# WWOL_phy.net
KiCad netlist of a schematic drawn in Altium Designer
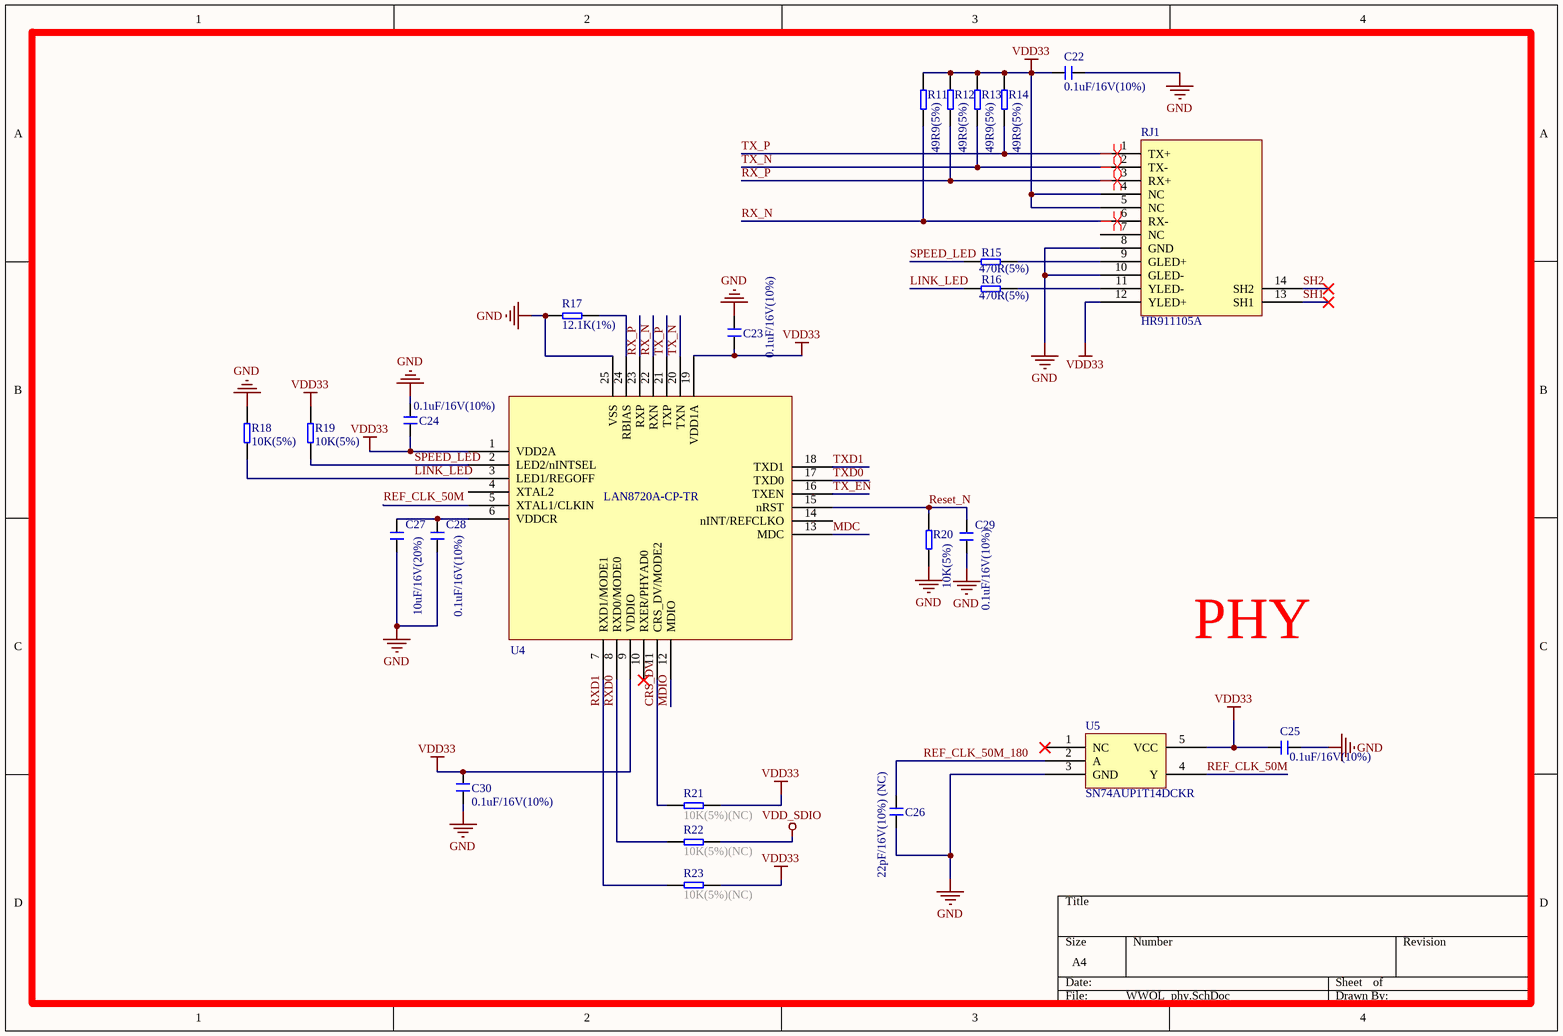
[diagram p0: WWOL_phy.SchDoc]

(export (version "E")
  (design (tool "Eeschema 10.0.6"))
  (components
    (comp (ref "C22")
      (value "0.1uF/16V(10%)")
      (footprint "C0402")
      (description "无极性贴片电容")
      (fields (field (name "版权归属") "源创客"))
      (libsource (lib "WWOL") (part "C"))
    )
    (comp (ref "C23")
      (value "0.1uF/16V(10%)")
      (footprint "C0402")
      (description "无极性贴片电容")
      (fields (field (name "版权归属") "源创客"))
      (libsource (lib "WWOL") (part "C"))
    )
    (comp (ref "C24")
      (value "0.1uF/16V(10%)")
      (footprint "C0402")
      (description "无极性贴片电容")
      (fields (field (name "版权归属") "源创客"))
      (libsource (lib "WWOL") (part "C"))
    )
    (comp (ref "C25")
      (value "0.1uF/16V(10%)")
      (footprint "C0402")
      (description "无极性贴片电容")
      (fields (field (name "版权归属") "源创客"))
      (libsource (lib "WWOL") (part "C"))
    )
    (comp (ref "C26")
      (value "22pF/16V(10%) (NC)")
      (footprint "C0402")
      (description "无极性贴片电容")
      (fields (field (name "版权归属") "源创客"))
      (libsource (lib "WWOL") (part "C"))
    )
    (comp (ref "C27")
      (value "10uF/16V(20%)")
      (footprint "C0402")
      (description "无极性贴片电容")
      (fields (field (name "版权归属") "源创客"))
      (libsource (lib "WWOL") (part "C"))
    )
    (comp (ref "C28")
      (value "0.1uF/16V(10%)")
      (footprint "C0402")
      (description "无极性贴片电容")
      (fields (field (name "版权归属") "源创客"))
      (libsource (lib "WWOL") (part "C"))
    )
    (comp (ref "C29")
      (value "0.1uF/16V(10%)")
      (footprint "C0402")
      (description "无极性贴片电容")
      (fields (field (name "版权归属") "源创客"))
      (libsource (lib "WWOL") (part "C"))
    )
    (comp (ref "C30")
      (value "0.1uF/16V(10%)")
      (footprint "C0402")
      (description "无极性贴片电容")
      (fields (field (name "版权归属") "源创客"))
      (libsource (lib "WWOL") (part "C"))
    )
    (comp (ref "R11")
      (value "49R9(5%)")
      (footprint "R0402")
      (description "贴片电阻")
      (libsource (lib "WWOL") (part "R"))
    )
    (comp (ref "R12")
      (value "49R9(5%)")
      (footprint "R0402")
      (description "贴片电阻")
      (libsource (lib "WWOL") (part "R"))
    )
    (comp (ref "R13")
      (value "49R9(5%)")
      (footprint "R0402")
      (description "贴片电阻")
      (libsource (lib "WWOL") (part "R"))
    )
    (comp (ref "R14")
      (value "49R9(5%)")
      (footprint "R0402")
      (description "贴片电阻")
      (libsource (lib "WWOL") (part "R"))
    )
    (comp (ref "R15")
      (value "470R(5%)")
      (footprint "R0402")
      (description "贴片电阻")
      (libsource (lib "WWOL") (part "R"))
    )
    (comp (ref "R16")
      (value "470R(5%)")
      (footprint "R0402")
      (description "贴片电阻")
      (libsource (lib "WWOL") (part "R"))
    )
    (comp (ref "R17")
      (value "12.1K(1%)")
      (footprint "R0402")
      (description "贴片电阻")
      (libsource (lib "WWOL") (part "R"))
    )
    (comp (ref "R18")
      (value "10K(5%)")
      (footprint "R0402")
      (description "贴片电阻")
      (libsource (lib "WWOL") (part "R"))
    )
    (comp (ref "R19")
      (value "10K(5%)")
      (footprint "R0402")
      (description "贴片电阻")
      (libsource (lib "WWOL") (part "R"))
    )
    (comp (ref "R20")
      (value "10K(5%)")
      (footprint "R0402")
      (description "贴片电阻")
      (libsource (lib "WWOL") (part "R"))
    )
    (comp (ref "R21")
      (value "10K(5%)(NC)")
      (footprint "R0402")
      (description "贴片电阻")
      (libsource (lib "WWOL") (part "R"))
    )
    (comp (ref "R22")
      (value "10K(5%)(NC)")
      (footprint "R0402")
      (description "贴片电阻")
      (libsource (lib "WWOL") (part "R"))
    )
    (comp (ref "R23")
      (value "10K(5%)(NC)")
      (footprint "R0402")
      (description "贴片电阻")
      (libsource (lib "WWOL") (part "R"))
    )
    (comp (ref "RJ1")
      (value "HR911105A")
      (footprint "RJ-45A12")
      (description "带灯以太网接口")
      (libsource (lib "WWOL") (part "HR911105A"))
    )
    (comp (ref "U4")
      (value "LAN8720A-CP-TR")
      (footprint "QFN50P400X400X100_HS-25N")
      (description "以太网phy")
      (libsource (lib "WWOL") (part "LAN8720A-CP-TR"))
    )
    (comp (ref "U5")
      (value "SN74AUP1T14DCKR")
      (footprint "SC-70-5_L2.1-W1.3-P0.65-LS2.1-BR")
      (description "反相器")
      (libsource (lib "WWOL") (part "SN74AUP1T14DCKR"))
    )
  )
  (nets
    (net (code "1") (name "/CRS_DV") (class "Default")
      (node (ref "R21") (pin "1") (pinfunction "1_1") (pintype "passive"))
      (node (ref "U4") (pin "11") (pinfunction "CRS_DV/MODE2_11") (pintype "passive"))
    )
    (net (code "2") (name "/LINK_LED") (class "Default")
      (node (ref "R16") (pin "2") (pinfunction "2_2") (pintype "passive"))
      (node (ref "R18") (pin "2") (pinfunction "2_2") (pintype "passive"))
      (node (ref "U4") (pin "3") (pinfunction "LED1/REGOFF_3") (pintype "passive"))
    )
    (net (code "3") (name "/MDC") (class "Default")
      (node (ref "U4") (pin "13") (pinfunction "MDC_13") (pintype "passive"))
    )
    (net (code "4") (name "/MDIO") (class "Default")
      (node (ref "U4") (pin "12") (pinfunction "MDIO_12") (pintype "passive"))
    )
    (net (code "5") (name "/REF_CLK_50M") (class "Default")
      (node (ref "U4") (pin "5") (pinfunction "XTAL1/CLKIN_5") (pintype "passive"))
      (node (ref "U5") (pin "4") (pinfunction "Y_4") (pintype "passive"))
    )
    (net (code "6") (name "/REF_CLK_50M_180") (class "Default")
      (node (ref "C26") (pin "1") (pinfunction "1_1") (pintype "passive"))
      (node (ref "U5") (pin "2") (pinfunction "A_2") (pintype "passive"))
    )
    (net (code "7") (name "/RXD0") (class "Default")
      (node (ref "R22") (pin "1") (pinfunction "1_1") (pintype "passive"))
      (node (ref "U4") (pin "8") (pinfunction "RXD0/MODE0_8") (pintype "passive"))
    )
    (net (code "8") (name "/RXD1") (class "Default")
      (node (ref "R23") (pin "1") (pinfunction "1_1") (pintype "passive"))
      (node (ref "U4") (pin "7") (pinfunction "RXD1/MODE1_7") (pintype "passive"))
    )
    (net (code "9") (name "/RX_N") (class "Default")
      (node (ref "R11") (pin "2") (pinfunction "2_2") (pintype "passive"))
      (node (ref "RJ1") (pin "6") (pinfunction "RX-_6") (pintype "passive"))
      (node (ref "U4") (pin "22") (pinfunction "RXN_22") (pintype "passive"))
    )
    (net (code "10") (name "/RX_P") (class "Default")
      (node (ref "R12") (pin "2") (pinfunction "2_2") (pintype "passive"))
      (node (ref "RJ1") (pin "3") (pinfunction "RX+_3") (pintype "passive"))
      (node (ref "U4") (pin "23") (pinfunction "RXP_23") (pintype "passive"))
    )
    (net (code "11") (name "/Reset_N") (class "Default")
      (node (ref "C29") (pin "2") (pinfunction "2_2") (pintype "passive"))
      (node (ref "R20") (pin "2") (pinfunction "2_2") (pintype "passive"))
      (node (ref "U4") (pin "15") (pinfunction "nRST_15") (pintype "passive"))
    )
    (net (code "12") (name "/SH1") (class "Default")
      (node (ref "RJ1") (pin "13") (pinfunction "SH1_13") (pintype "passive+no_connect"))
    )
    (net (code "13") (name "/SH2") (class "Default")
      (node (ref "RJ1") (pin "14") (pinfunction "SH2_14") (pintype "passive+no_connect"))
    )
    (net (code "14") (name "/SPEED_LED") (class "Default")
      (node (ref "R15") (pin "2") (pinfunction "2_2") (pintype "passive"))
      (node (ref "R19") (pin "2") (pinfunction "2_2") (pintype "passive"))
      (node (ref "U4") (pin "2") (pinfunction "LED2/nINTSEL_2") (pintype "passive"))
    )
    (net (code "15") (name "/TXD0") (class "Default")
      (node (ref "U4") (pin "17") (pinfunction "TXD0_17") (pintype "passive"))
    )
    (net (code "16") (name "/TXD1") (class "Default")
      (node (ref "U4") (pin "18") (pinfunction "TXD1_18") (pintype "passive"))
    )
    (net (code "17") (name "/TX_EN") (class "Default")
      (node (ref "U4") (pin "16") (pinfunction "TXEN_16") (pintype "passive"))
    )
    (net (code "18") (name "/TX_N") (class "Default")
      (node (ref "R13") (pin "2") (pinfunction "2_2") (pintype "passive"))
      (node (ref "RJ1") (pin "2") (pinfunction "TX-_2") (pintype "passive"))
      (node (ref "U4") (pin "20") (pinfunction "TXN_20") (pintype "passive"))
    )
    (net (code "19") (name "/TX_P") (class "Default")
      (node (ref "R14") (pin "2") (pinfunction "2_2") (pintype "passive"))
      (node (ref "RJ1") (pin "1") (pinfunction "TX+_1") (pintype "passive"))
      (node (ref "U4") (pin "21") (pinfunction "TXP_21") (pintype "passive"))
    )
    (net (code "20") (name "GND") (class "Default")
      (node (ref "C22") (pin "2") (pinfunction "2_2") (pintype "passive"))
      (node (ref "C23") (pin "2") (pinfunction "2_2") (pintype "passive"))
      (node (ref "C24") (pin "1") (pinfunction "1_1") (pintype "passive"))
      (node (ref "C25") (pin "1") (pinfunction "1_1") (pintype "passive"))
      (node (ref "C26") (pin "2") (pinfunction "2_2") (pintype "passive"))
      (node (ref "C27") (pin "1") (pinfunction "1_1") (pintype "passive"))
      (node (ref "C28") (pin "1") (pinfunction "1_1") (pintype "passive"))
      (node (ref "C29") (pin "1") (pinfunction "1_1") (pintype "passive"))
      (node (ref "C30") (pin "1") (pinfunction "1_1") (pintype "passive"))
      (node (ref "R17") (pin "2") (pinfunction "2_2") (pintype "passive"))
      (node (ref "R18") (pin "1") (pinfunction "1_1") (pintype "passive"))
      (node (ref "R20") (pin "1") (pinfunction "1_1") (pintype "passive"))
      (node (ref "RJ1") (pin "10") (pinfunction "GLED-_10") (pintype "passive"))
      (node (ref "RJ1") (pin "8") (pinfunction "GND_8") (pintype "passive"))
      (node (ref "U4") (pin "25") (pinfunction "VSS_25") (pintype "passive"))
      (node (ref "U5") (pin "3") (pinfunction "GND_3") (pintype "passive"))
    )
    (net (code "21") (name "Net-(RJ1-GLED+)") (class "Default")
      (node (ref "R15") (pin "1") (pinfunction "1_1") (pintype "passive"))
      (node (ref "RJ1") (pin "9") (pinfunction "GLED+_9") (pintype "passive"))
    )
    (net (code "22") (name "Net-(RJ1-YLED-)") (class "Default")
      (node (ref "R16") (pin "1") (pinfunction "1_1") (pintype "passive"))
      (node (ref "RJ1") (pin "11") (pinfunction "YLED-_11") (pintype "passive"))
    )
    (net (code "23") (name "Net-(U4-RBIAS)") (class "Default")
      (node (ref "R17") (pin "1") (pinfunction "1_1") (pintype "passive"))
      (node (ref "U4") (pin "24") (pinfunction "RBIAS_24") (pintype "passive"))
    )
    (net (code "24") (name "Net-(U4-VDDCR)") (class "Default")
      (node (ref "C27") (pin "2") (pinfunction "2_2") (pintype "passive"))
      (node (ref "C28") (pin "2") (pinfunction "2_2") (pintype "passive"))
      (node (ref "U4") (pin "6") (pinfunction "VDDCR_6") (pintype "passive"))
    )
    (net (code "25") (name "VDD33") (class "Default")
      (node (ref "C22") (pin "1") (pinfunction "1_1") (pintype "passive"))
      (node (ref "C23") (pin "1") (pinfunction "1_1") (pintype "passive"))
      (node (ref "C24") (pin "2") (pinfunction "2_2") (pintype "passive"))
      (node (ref "C25") (pin "2") (pinfunction "2_2") (pintype "passive"))
      (node (ref "C30") (pin "2") (pinfunction "2_2") (pintype "passive"))
      (node (ref "R11") (pin "1") (pinfunction "1_1") (pintype "passive"))
      (node (ref "R12") (pin "1") (pinfunction "1_1") (pintype "passive"))
      (node (ref "R13") (pin "1") (pinfunction "1_1") (pintype "passive"))
      (node (ref "R14") (pin "1") (pinfunction "1_1") (pintype "passive"))
      (node (ref "R19") (pin "1") (pinfunction "1_1") (pintype "passive"))
      (node (ref "R21") (pin "2") (pinfunction "2_2") (pintype "passive"))
      (node (ref "R23") (pin "2") (pinfunction "2_2") (pintype "passive"))
      (node (ref "RJ1") (pin "12") (pinfunction "YLED+_12") (pintype "passive"))
      (node (ref "RJ1") (pin "4") (pinfunction "NC_4") (pintype "passive"))
      (node (ref "RJ1") (pin "5") (pinfunction "NC_5") (pintype "passive"))
      (node (ref "U4") (pin "1") (pinfunction "VDD2A_1") (pintype "passive"))
      (node (ref "U4") (pin "19") (pinfunction "VDD1A_19") (pintype "passive"))
      (node (ref "U4") (pin "9") (pinfunction "VDDIO_9") (pintype "passive"))
      (node (ref "U5") (pin "5") (pinfunction "VCC_5") (pintype "passive"))
    )
    (net (code "26") (name "VDD_SDIO") (class "Default")
      (node (ref "R22") (pin "2") (pinfunction "2_2") (pintype "passive"))
    )
    (net (code "27") (name "unconnected-(RJ1-NC-Pad7)") (class "Default")
      (node (ref "RJ1") (pin "7") (pinfunction "NC_7") (pintype "passive"))
    )
    (net (code "28") (name "unconnected-(U4-RXER{slash}PHYAD0-Pad10)") (class "Default")
      (node (ref "U4") (pin "10") (pinfunction "RXER/PHYAD0_10") (pintype "passive+no_connect"))
    )
    (net (code "29") (name "unconnected-(U4-XTAL2-Pad4)") (class "Default")
      (node (ref "U4") (pin "4") (pinfunction "XTAL2_4") (pintype "passive"))
    )
    (net (code "30") (name "unconnected-(U4-nINT{slash}REFCLKO-Pad14)") (class "Default")
      (node (ref "U4") (pin "14") (pinfunction "nINT/REFCLKO_14") (pintype "passive"))
    )
    (net (code "31") (name "unconnected-(U5-NC-Pad1)") (class "Default")
      (node (ref "U5") (pin "1") (pinfunction "NC_1") (pintype "passive+no_connect"))
    )
  )
)
